# MCU.net
KiCad netlist of a schematic drawn in Altium Designer
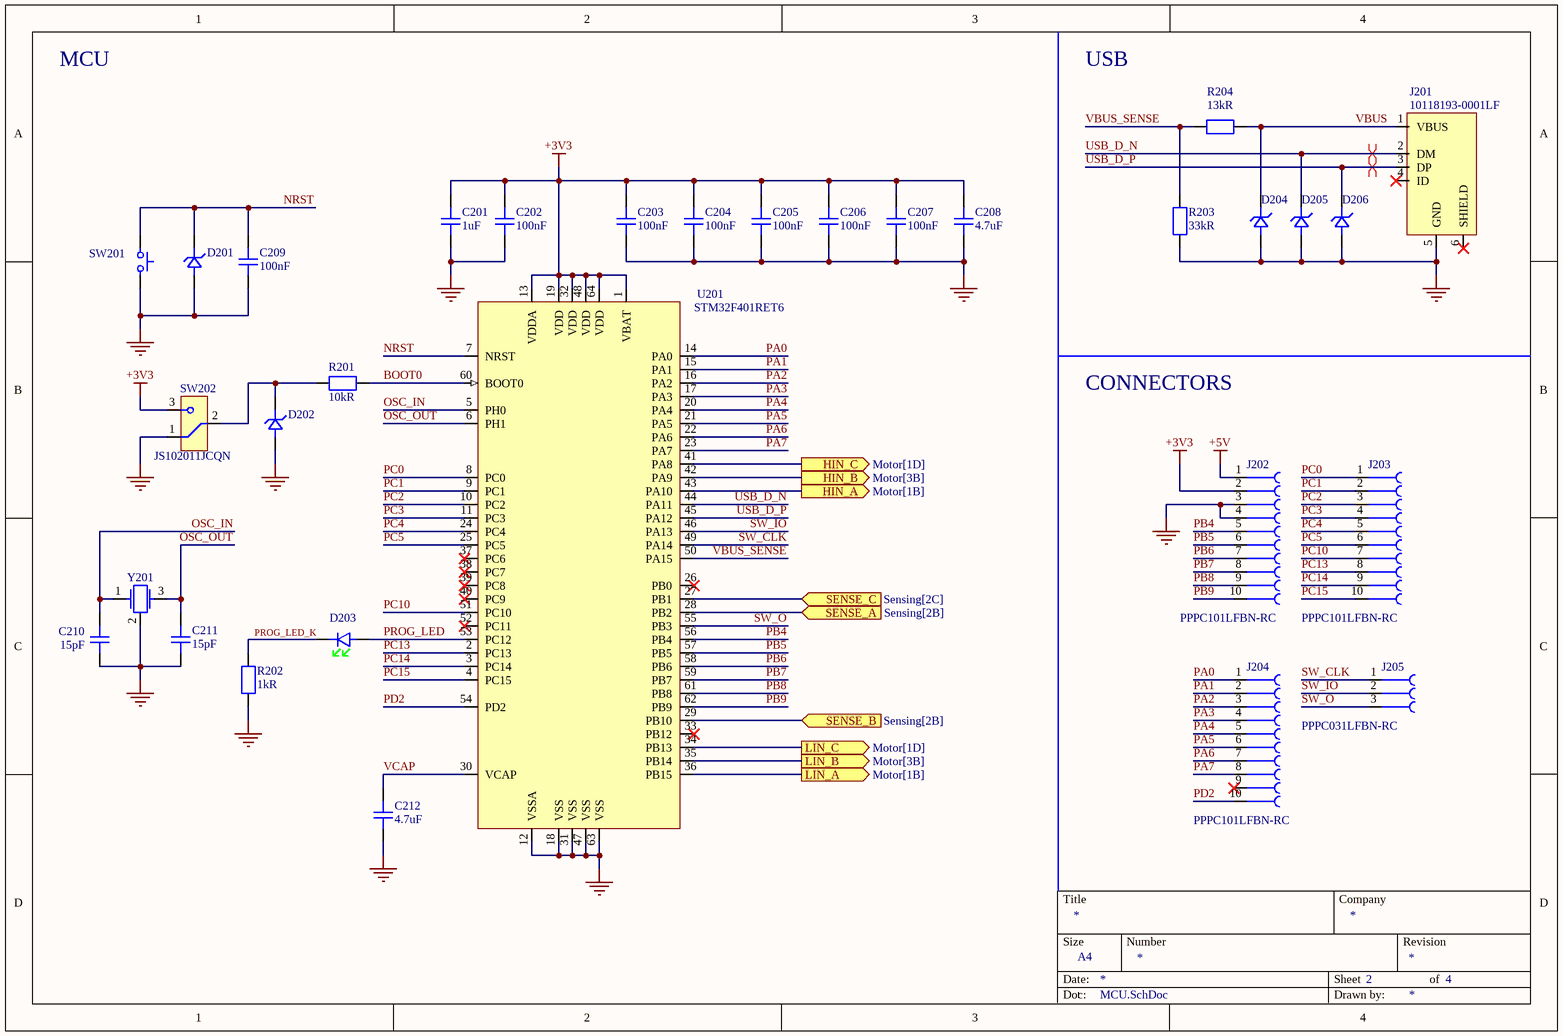
[diagram p0: MCU.SchDoc]

(export (version "E")
  (design (tool "Eeschema 10.0.6"))
  (components
    (comp (ref "C201")
      (value "1uF")
      (footprint "C_Yageo_CC_0603_A")
      (description "Multilayer Ceramic Capacitor, 1 uF, 16 V, ± 10%, X7R, 0603 [1608 Metric]")
      (fields (field (name "TOLERANCE") "10%") (field (name "VOLTAGE") "16V"))
      (libsource (lib "Dennis Micro Computers") (part "C"))
    )
    (comp (ref "C202")
      (value "100nF")
      (footprint "C_Yageo_CC_0402_A")
      (description "Multilayer Ceramic Capacitor, 0.1 uF, 10 V, ± 20%, X7R, 0402 [1005 Metric]")
      (fields (field (name "TOLERANCE") "20%") (field (name "Comment") "CC0402MRX5R6BB104"))
      (libsource (lib "Dennis Micro Computers") (part "C"))
    )
    (comp (ref "C203")
      (value "100nF")
      (footprint "C_Yageo_CC_0402_A")
      (description "Multilayer Ceramic Capacitor, 0.1 uF, 10 V, ± 20%, X7R, 0402 [1005 Metric]")
      (fields (field (name "TOLERANCE") "20%") (field (name "Comment") "CC0402MRX5R6BB104"))
      (libsource (lib "Dennis Micro Computers") (part "C"))
    )
    (comp (ref "C204")
      (value "100nF")
      (footprint "C_Yageo_CC_0402_A")
      (description "Multilayer Ceramic Capacitor, 0.1 uF, 10 V, ± 20%, X7R, 0402 [1005 Metric]")
      (fields (field (name "TOLERANCE") "20%") (field (name "Comment") "CC0402MRX5R6BB104"))
      (libsource (lib "Dennis Micro Computers") (part "C"))
    )
    (comp (ref "C205")
      (value "100nF")
      (footprint "C_Yageo_CC_0402_A")
      (description "Multilayer Ceramic Capacitor, 0.1 uF, 10 V, ± 20%, X7R, 0402 [1005 Metric]")
      (fields (field (name "TOLERANCE") "20%") (field (name "Comment") "CC0402MRX5R6BB104"))
      (libsource (lib "Dennis Micro Computers") (part "C"))
    )
    (comp (ref "C206")
      (value "100nF")
      (footprint "C_Yageo_CC_0402_A")
      (description "Multilayer Ceramic Capacitor, 0.1 uF, 10 V, ± 20%, X7R, 0402 [1005 Metric]")
      (fields (field (name "TOLERANCE") "20%") (field (name "Comment") "CC0402MRX5R6BB104"))
      (libsource (lib "Dennis Micro Computers") (part "C"))
    )
    (comp (ref "C207")
      (value "100nF")
      (footprint "C_Yageo_CC_0402_A")
      (description "Multilayer Ceramic Capacitor, 0.1 uF, 10 V, ± 20%, X7R, 0402 [1005 Metric]")
      (fields (field (name "TOLERANCE") "20%") (field (name "Comment") "CC0402MRX5R6BB104"))
      (libsource (lib "Dennis Micro Computers") (part "C"))
    )
    (comp (ref "C208")
      (value "4.7uF")
      (footprint "C_Yageo_CC_0402_A")
      (description "Multilayer Ceramic Capacitor, 4.7 uF, 50 V, ± 10%, X5R, 0402 [1005 Metric]")
      (fields (field (name "TOLERANCE") "20%") (field (name "Comment") "CC0402MRX5R6BB475"))
      (libsource (lib "Dennis Micro Computers") (part "C"))
    )
    (comp (ref "C209")
      (value "100nF")
      (footprint "C_Yageo_CC_0402_A")
      (description "Multilayer Ceramic Capacitor, 0.1 uF, 10 V, ± 20%, X7R, 0402 [1005 Metric]")
      (fields (field (name "TOLERANCE") "20%") (field (name "Comment") "CC0402MRX5R6BB104"))
      (libsource (lib "Dennis Micro Computers") (part "C"))
    )
    (comp (ref "C210")
      (value "15pF")
      (footprint "C_Yageo_CC_0402_A")
      (description "Multilayer Ceramic Capacitor, 15 pF, 10 V, ± 5%, X7R, 0402 [1005 Metric]")
      (fields (field (name "TOLERANCE") "5%") (field (name "VOLTAGE") "50V"))
      (libsource (lib "Dennis Micro Computers") (part "C"))
    )
    (comp (ref "C211")
      (value "15pF")
      (footprint "C_Yageo_CC_0402_A")
      (description "Multilayer Ceramic Capacitor, 15 pF, 10 V, ± 5%, X7R, 0402 [1005 Metric]")
      (fields (field (name "TOLERANCE") "5%") (field (name "VOLTAGE") "50V"))
      (libsource (lib "Dennis Micro Computers") (part "C"))
    )
    (comp (ref "C212")
      (value "4.7uF")
      (footprint "C_Yageo_CC_0402_A")
      (description "Multilayer Ceramic Capacitor, 4.7 uF, 50 V, ± 10%, X5R, 0402 [1005 Metric]")
      (fields (field (name "TOLERANCE") "20%") (field (name "Comment") "CC0402MRX5R6BB475"))
      (libsource (lib "Dennis Micro Computers") (part "C"))
    )
    (comp (ref "D201")
      (value "D5V0F1U2S9-7")
      (footprint "D_TVS_Uni_Diodes_SOD-923_B")
      (description "Diode TVS Dual Uni-Dir 5.5V 250000W 2-Pin SOD-923 T/R")
      (libsource (lib "Dennis Micro Computers") (part "D_TVS_Uni"))
    )
    (comp (ref "D202")
      (value "D5V0F1U2S9-7")
      (footprint "D_TVS_Uni_Diodes_SOD-923_B")
      (description "Diode TVS Dual Uni-Dir 5.5V 250000W 2-Pin SOD-923 T/R")
      (libsource (lib "Dennis Micro Computers") (part "D_TVS_Uni"))
    )
    (comp (ref "D203")
      (value "150080GS75000")
      (footprint "D_LED_We_150080GS75000")
      (description "WURTH ELEKTRONIK - 150080GS75000 - LED, Green, SMD, 0805, 30 mA, 3.2 V, 520 nm")
      (libsource (lib "Dennis Micro Computers") (part "D_LED_Green"))
    )
    (comp (ref "D204")
      (value "D5V0F1U2S9-7")
      (footprint "D_TVS_Uni_Diodes_SOD-923_B")
      (description "Diode TVS Dual Uni-Dir 5.5V 250000W 2-Pin SOD-923 T/R")
      (libsource (lib "Dennis Micro Computers") (part "D_TVS_Uni"))
    )
    (comp (ref "D205")
      (value "D5V0F1U2S9-7")
      (footprint "D_TVS_Uni_Diodes_SOD-923_B")
      (description "Diode TVS Dual Uni-Dir 5.5V 250000W 2-Pin SOD-923 T/R")
      (libsource (lib "Dennis Micro Computers") (part "D_TVS_Uni"))
    )
    (comp (ref "D206")
      (value "D5V0F1U2S9-7")
      (footprint "D_TVS_Uni_Diodes_SOD-923_B")
      (description "Diode TVS Dual Uni-Dir 5.5V 250000W 2-Pin SOD-923 T/R")
      (libsource (lib "Dennis Micro Computers") (part "D_TVS_Uni"))
    )
    (comp (ref "J201")
      (value "10118193-0001LF")
      (footprint "J_USB_Micro-B_Amphenol_10118193-0001LF")
      (description "Usb Connector, 5 Contact(S), Female, Right Angle, Surface Mount Terminal, Locking, Receptacle")
      (libsource (lib "Dennis Micro Computers") (part "J_USB2_B_Micro"))
    )
    (comp (ref "J202")
      (value "PPPC101LFBN-RC")
      (footprint "J_Sullins_01x07_Socket_2.54mm")
      (description "10 Position Total Single Row 2.54 mm Pitch Straight Female Header")
      (libsource (lib "Dennis Micro Computers") (part "J_01x10_Socket"))
    )
    (comp (ref "J203")
      (value "PPPC101LFBN-RC")
      (footprint "J_Sullins_01x07_Socket_2.54mm")
      (description "10 Position Total Single Row 2.54 mm Pitch Straight Female Header")
      (libsource (lib "Dennis Micro Computers") (part "J_01x10_Socket"))
    )
    (comp (ref "J204")
      (value "PPPC101LFBN-RC")
      (footprint "J_Sullins_01x07_Socket_2.54mm")
      (description "10 Position Total Single Row 2.54 mm Pitch Straight Female Header")
      (libsource (lib "Dennis Micro Computers") (part "J_01x10_Socket"))
    )
    (comp (ref "J205")
      (value "PPPC031LFBN-RC")
      (footprint "J_Sullins_01x03_Socket_2.54mm")
      (description "3 Position Total Single Row 2.54 mm Pitch Straight Female Header")
      (libsource (lib "Dennis Micro Computers") (part "J_01x03_Socket"))
    )
    (comp (ref "R201")
      (value "10kR")
      (footprint "R_Yageo_RCL_0402_A")
      (description "SMD Chip Resistor, 10 kOhm, ± 1%, 62.5 mW, 0402 [1005 Metric], Thick Film, General Purpose")
      (fields (field (name "TOLERANCE") "1%") (field (name "Comment") "RC0402FR-0710KL"))
      (libsource (lib "Dennis Micro Computers") (part "R"))
    )
    (comp (ref "R202")
      (value "1kR")
      (footprint "R_Yageo_RCL_0402_A")
      (description "SMD Chip Resistor, 1 kOhm, ± 1%, 62.5 mW, 0402 [1005 Metric], Thick Film, General Purpose")
      (fields (field (name "TOLERANCE") "1%") (field (name "Comment") "RC0402FR-071KL"))
      (libsource (lib "Dennis Micro Computers") (part "R"))
    )
    (comp (ref "R203")
      (value "33kR")
      (footprint "R_Yageo_RCL_0402_A")
      (description "SMD Chip Resistor, 33 kOhm, ± 1%, 63 mW, 0402 [1005 Metric], Thick Film, General Purpose")
      (fields (field (name "TOLERANCE") "1%") (field (name "Comment") "RC0402FR-0733KL"))
      (libsource (lib "Dennis Micro Computers") (part "R"))
    )
    (comp (ref "R204")
      (value "13kR")
      (footprint "R_Yageo_RCL_0402_A")
      (description "SMD Chip Resistor, 13 kOhm, ± 1%, 63 mW, 0402 [1005 Metric], Thick Film, General Purpose")
      (fields (field (name "TOLERANCE") "1%") (field (name "Comment") "RC0402FR-0713KL"))
      (libsource (lib "Dennis Micro Computers") (part "R"))
    )
    (comp (ref "SW201")
      (value "PTS647SN50SMTR2LFS")
      (footprint "SW_Tactitle_SPST_C&K_PTS647SN50SMTR2LFS")
      (description "Switch Tactile N.O. SPST Round Button Gull Wing 0.05A 12VDC 100000Cycles 0.98N SMD T/R")
      (libsource (lib "Dennis Micro Computers") (part "SW_Tactile_SPST"))
    )
    (comp (ref "SW202")
      (value "JS102011JCQN")
      (footprint "SW_Slide_C&K_JS102011JCQN")
      (description "JS Series Sub-Miniature Slide Switch SPDT On-On Top Slide 0.3A 6VDC J-Lead Surface Mount T/R")
      (libsource (lib "Dennis Micro Computers") (part "SW_Slide_SPDT"))
    )
    (comp (ref "U201")
      (value "STM32F401RET6")
      (footprint "U_ST_STM32F401xD/xE_B")
      (description "MCU 32-bit STM32 ARM Cortex M4 RISC 512KB Flash 1.8V/2.5V/3.3V 64-Pin LQFP Tray")
      (libsource (lib "Dennis Micro Computers") (part "U_STM32F401xD/xE"))
    )
    (comp (ref "Y201")
      (value "ECS-240-12-37B-CKY-TR")
      (footprint "Y_Crystal_GND24_ECS_240-12-37B-CKY-TR")
      (description "Crystal 24MHz ±10ppm (Tol) ±10ppm (Stability) 12pF FUND 50Ohm 4-Pin Mini-CSMD T/R")
      (libsource (lib "Dennis Micro Computers") (part "Y_Crystal_GND24"))
    )
  )
  (nets
    (net (code "1") (name "+3V3") (class "Default")
      (node (ref "C201") (pin "2") (pinfunction "2_2") (pintype "passive"))
      (node (ref "C202") (pin "2") (pinfunction "2_2") (pintype "passive"))
      (node (ref "C203") (pin "2") (pinfunction "2_2") (pintype "passive"))
      (node (ref "C204") (pin "2") (pinfunction "2_2") (pintype "passive"))
      (node (ref "C205") (pin "2") (pinfunction "2_2") (pintype "passive"))
      (node (ref "C206") (pin "2") (pinfunction "2_2") (pintype "passive"))
      (node (ref "C207") (pin "2") (pinfunction "2_2") (pintype "passive"))
      (node (ref "C208") (pin "2") (pinfunction "2_2") (pintype "passive"))
      (node (ref "J202") (pin "2") (pinfunction "2_2") (pintype "passive"))
      (node (ref "SW202") (pin "3") (pinfunction "3_3") (pintype "passive"))
      (node (ref "U201") (pin "1") (pinfunction "VBAT_1") (pintype "power_in"))
      (node (ref "U201") (pin "13") (pinfunction "VDDA_13") (pintype "power_in"))
      (node (ref "U201") (pin "19") (pinfunction "VDD_19") (pintype "power_in"))
      (node (ref "U201") (pin "32") (pinfunction "VDD_32") (pintype "power_in"))
      (node (ref "U201") (pin "48") (pinfunction "VDD_48") (pintype "power_in"))
      (node (ref "U201") (pin "64") (pinfunction "VDD_64") (pintype "power_in"))
    )
    (net (code "2") (name "+5V") (class "Default")
      (node (ref "J202") (pin "1") (pinfunction "1_1") (pintype "passive"))
    )
    (net (code "3") (name "/BOOT0") (class "Default")
      (node (ref "R201") (pin "2") (pinfunction "2_2") (pintype "passive"))
      (node (ref "U201") (pin "60") (pinfunction "BOOT0_60") (pintype "input"))
    )
    (net (code "4") (name "/HIN_A") (class "Default")
      (node (ref "U201") (pin "43") (pinfunction "PA10_43") (pintype "bidirectional"))
    )
    (net (code "5") (name "/HIN_B") (class "Default")
      (node (ref "U201") (pin "42") (pinfunction "PA9_42") (pintype "bidirectional"))
    )
    (net (code "6") (name "/HIN_C") (class "Default")
      (node (ref "U201") (pin "41") (pinfunction "PA8_41") (pintype "bidirectional"))
    )
    (net (code "7") (name "/LIN_A") (class "Default")
      (node (ref "U201") (pin "36") (pinfunction "PB15_36") (pintype "bidirectional"))
    )
    (net (code "8") (name "/LIN_B") (class "Default")
      (node (ref "U201") (pin "35") (pinfunction "PB14_35") (pintype "bidirectional"))
    )
    (net (code "9") (name "/LIN_C") (class "Default")
      (node (ref "U201") (pin "34") (pinfunction "PB13_34") (pintype "bidirectional"))
    )
    (net (code "10") (name "/NRST") (class "Default")
      (node (ref "C209") (pin "2") (pinfunction "2_2") (pintype "passive"))
      (node (ref "D201") (pin "1") (pinfunction "1_1") (pintype "passive"))
      (node (ref "SW201") (pin "1") (pinfunction "1_1") (pintype "passive"))
      (node (ref "U201") (pin "7") (pinfunction "NRST_7") (pintype "bidirectional"))
    )
    (net (code "11") (name "/OSC_IN") (class "Default")
      (node (ref "C210") (pin "2") (pinfunction "2_2") (pintype "passive"))
      (node (ref "U201") (pin "5") (pinfunction "PH0_5") (pintype "bidirectional"))
      (node (ref "Y201") (pin "1") (pinfunction "1_1") (pintype "passive"))
    )
    (net (code "12") (name "/OSC_OUT") (class "Default")
      (node (ref "C211") (pin "2") (pinfunction "2_2") (pintype "passive"))
      (node (ref "U201") (pin "6") (pinfunction "PH1_6") (pintype "bidirectional"))
      (node (ref "Y201") (pin "3") (pinfunction "3_3") (pintype "passive"))
    )
    (net (code "13") (name "/PA0") (class "Default")
      (node (ref "J204") (pin "1") (pinfunction "1_1") (pintype "passive"))
      (node (ref "U201") (pin "14") (pinfunction "PA0_14") (pintype "bidirectional"))
    )
    (net (code "14") (name "/PA1") (class "Default")
      (node (ref "J204") (pin "2") (pinfunction "2_2") (pintype "passive"))
      (node (ref "U201") (pin "15") (pinfunction "PA1_15") (pintype "bidirectional"))
    )
    (net (code "15") (name "/PA2") (class "Default")
      (node (ref "J204") (pin "3") (pinfunction "3_3") (pintype "passive"))
      (node (ref "U201") (pin "16") (pinfunction "PA2_16") (pintype "bidirectional"))
    )
    (net (code "16") (name "/PA3") (class "Default")
      (node (ref "J204") (pin "4") (pinfunction "4_4") (pintype "passive"))
      (node (ref "U201") (pin "17") (pinfunction "PA3_17") (pintype "bidirectional"))
    )
    (net (code "17") (name "/PA4") (class "Default")
      (node (ref "J204") (pin "5") (pinfunction "5_5") (pintype "passive"))
      (node (ref "U201") (pin "20") (pinfunction "PA4_20") (pintype "bidirectional"))
    )
    (net (code "18") (name "/PA5") (class "Default")
      (node (ref "J204") (pin "6") (pinfunction "6_6") (pintype "passive"))
      (node (ref "U201") (pin "21") (pinfunction "PA5_21") (pintype "bidirectional"))
    )
    (net (code "19") (name "/PA6") (class "Default")
      (node (ref "J204") (pin "7") (pinfunction "7_7") (pintype "passive"))
      (node (ref "U201") (pin "22") (pinfunction "PA6_22") (pintype "bidirectional"))
    )
    (net (code "20") (name "/PA7") (class "Default")
      (node (ref "J204") (pin "8") (pinfunction "8_8") (pintype "passive"))
      (node (ref "U201") (pin "23") (pinfunction "PA7_23") (pintype "bidirectional"))
    )
    (net (code "21") (name "/PB4") (class "Default")
      (node (ref "J202") (pin "5") (pinfunction "5_5") (pintype "passive"))
      (node (ref "U201") (pin "56") (pinfunction "PB4_56") (pintype "bidirectional"))
    )
    (net (code "22") (name "/PB5") (class "Default")
      (node (ref "J202") (pin "6") (pinfunction "6_6") (pintype "passive"))
      (node (ref "U201") (pin "57") (pinfunction "PB5_57") (pintype "bidirectional"))
    )
    (net (code "23") (name "/PB6") (class "Default")
      (node (ref "J202") (pin "7") (pinfunction "7_7") (pintype "passive"))
      (node (ref "U201") (pin "58") (pinfunction "PB6_58") (pintype "bidirectional"))
    )
    (net (code "24") (name "/PB7") (class "Default")
      (node (ref "J202") (pin "8") (pinfunction "8_8") (pintype "passive"))
      (node (ref "U201") (pin "59") (pinfunction "PB7_59") (pintype "bidirectional"))
    )
    (net (code "25") (name "/PB8") (class "Default")
      (node (ref "J202") (pin "9") (pinfunction "9_9") (pintype "passive"))
      (node (ref "U201") (pin "61") (pinfunction "PB8_61") (pintype "bidirectional"))
    )
    (net (code "26") (name "/PB9") (class "Default")
      (node (ref "J202") (pin "10") (pinfunction "10_10") (pintype "passive"))
      (node (ref "U201") (pin "62") (pinfunction "PB9_62") (pintype "bidirectional"))
    )
    (net (code "27") (name "/PC0") (class "Default")
      (node (ref "J203") (pin "1") (pinfunction "1_1") (pintype "passive"))
      (node (ref "U201") (pin "8") (pinfunction "PC0_8") (pintype "bidirectional"))
    )
    (net (code "28") (name "/PC1") (class "Default")
      (node (ref "J203") (pin "2") (pinfunction "2_2") (pintype "passive"))
      (node (ref "U201") (pin "9") (pinfunction "PC1_9") (pintype "bidirectional"))
    )
    (net (code "29") (name "/PC2") (class "Default")
      (node (ref "J203") (pin "3") (pinfunction "3_3") (pintype "passive"))
      (node (ref "U201") (pin "10") (pinfunction "PC2_10") (pintype "bidirectional"))
    )
    (net (code "30") (name "/PC3") (class "Default")
      (node (ref "J203") (pin "4") (pinfunction "4_4") (pintype "passive"))
      (node (ref "U201") (pin "11") (pinfunction "PC3_11") (pintype "bidirectional"))
    )
    (net (code "31") (name "/PC4") (class "Default")
      (node (ref "J203") (pin "5") (pinfunction "5_5") (pintype "passive"))
      (node (ref "U201") (pin "24") (pinfunction "PC4_24") (pintype "bidirectional"))
    )
    (net (code "32") (name "/PC5") (class "Default")
      (node (ref "J203") (pin "6") (pinfunction "6_6") (pintype "passive"))
      (node (ref "U201") (pin "25") (pinfunction "PC5_25") (pintype "bidirectional"))
    )
    (net (code "33") (name "/PC10") (class "Default")
      (node (ref "J203") (pin "7") (pinfunction "7_7") (pintype "passive"))
      (node (ref "U201") (pin "51") (pinfunction "PC10_51") (pintype "bidirectional"))
    )
    (net (code "34") (name "/PC13") (class "Default")
      (node (ref "J203") (pin "8") (pinfunction "8_8") (pintype "passive"))
      (node (ref "U201") (pin "2") (pinfunction "PC13_2") (pintype "bidirectional"))
    )
    (net (code "35") (name "/PC14") (class "Default")
      (node (ref "J203") (pin "9") (pinfunction "9_9") (pintype "passive"))
      (node (ref "U201") (pin "3") (pinfunction "PC14_3") (pintype "bidirectional"))
    )
    (net (code "36") (name "/PC15") (class "Default")
      (node (ref "J203") (pin "10") (pinfunction "10_10") (pintype "passive"))
      (node (ref "U201") (pin "4") (pinfunction "PC15_4") (pintype "bidirectional"))
    )
    (net (code "37") (name "/PD2") (class "Default")
      (node (ref "J204") (pin "10") (pinfunction "10_10") (pintype "passive"))
      (node (ref "U201") (pin "54") (pinfunction "PD2_54") (pintype "bidirectional"))
    )
    (net (code "38") (name "/PROG_LED") (class "Default")
      (node (ref "D203") (pin "1") (pinfunction "1_1") (pintype "passive"))
      (node (ref "U201") (pin "53") (pinfunction "PC12_53") (pintype "bidirectional"))
    )
    (net (code "39") (name "/PROG_LED_K") (class "Default")
      (node (ref "D203") (pin "2") (pinfunction "2_2") (pintype "passive"))
      (node (ref "R202") (pin "2") (pinfunction "2_2") (pintype "passive"))
    )
    (net (code "40") (name "/SENSE_A") (class "Default")
      (node (ref "U201") (pin "28") (pinfunction "PB2_28") (pintype "bidirectional"))
    )
    (net (code "41") (name "/SENSE_B") (class "Default")
      (node (ref "U201") (pin "29") (pinfunction "PB10_29") (pintype "bidirectional"))
    )
    (net (code "42") (name "/SENSE_C") (class "Default")
      (node (ref "U201") (pin "27") (pinfunction "PB1_27") (pintype "bidirectional"))
    )
    (net (code "43") (name "/SW_CLK") (class "Default")
      (node (ref "J205") (pin "1") (pinfunction "1_1") (pintype "passive"))
      (node (ref "U201") (pin "49") (pinfunction "PA14_49") (pintype "bidirectional"))
    )
    (net (code "44") (name "/SW_IO") (class "Default")
      (node (ref "J205") (pin "2") (pinfunction "2_2") (pintype "passive"))
      (node (ref "U201") (pin "46") (pinfunction "PA13_46") (pintype "bidirectional"))
    )
    (net (code "45") (name "/SW_O") (class "Default")
      (node (ref "J205") (pin "3") (pinfunction "3_3") (pintype "passive"))
      (node (ref "U201") (pin "55") (pinfunction "PB3_55") (pintype "bidirectional"))
    )
    (net (code "46") (name "/USB_D_N") (class "Default")
      (node (ref "D205") (pin "1") (pinfunction "1_1") (pintype "passive"))
      (node (ref "J201") (pin "2") (pinfunction "DM_2") (pintype "bidirectional"))
      (node (ref "U201") (pin "44") (pinfunction "PA11_44") (pintype "bidirectional"))
    )
    (net (code "47") (name "/USB_D_P") (class "Default")
      (node (ref "D206") (pin "1") (pinfunction "1_1") (pintype "passive"))
      (node (ref "J201") (pin "3") (pinfunction "DP_3") (pintype "bidirectional"))
      (node (ref "U201") (pin "45") (pinfunction "PA12_45") (pintype "bidirectional"))
    )
    (net (code "48") (name "/VBUS") (class "Default")
      (node (ref "D204") (pin "1") (pinfunction "1_1") (pintype "passive"))
      (node (ref "J201") (pin "1") (pinfunction "VBUS_1") (pintype "power_in"))
      (node (ref "R204") (pin "2") (pinfunction "2_2") (pintype "passive"))
    )
    (net (code "49") (name "/VBUS_SENSE") (class "Default")
      (node (ref "R203") (pin "2") (pinfunction "2_2") (pintype "passive"))
      (node (ref "R204") (pin "1") (pinfunction "1_1") (pintype "passive"))
      (node (ref "U201") (pin "50") (pinfunction "PA15_50") (pintype "bidirectional"))
    )
    (net (code "50") (name "/VCAP") (class "Default")
      (node (ref "C212") (pin "2") (pinfunction "2_2") (pintype "passive"))
      (node (ref "U201") (pin "30") (pinfunction "VCAP_30") (pintype "power_in"))
    )
    (net (code "51") (name "GND") (class "Default")
      (node (ref "C201") (pin "1") (pinfunction "1_1") (pintype "passive"))
      (node (ref "C202") (pin "1") (pinfunction "1_1") (pintype "passive"))
      (node (ref "C203") (pin "1") (pinfunction "1_1") (pintype "passive"))
      (node (ref "C204") (pin "1") (pinfunction "1_1") (pintype "passive"))
      (node (ref "C205") (pin "1") (pinfunction "1_1") (pintype "passive"))
      (node (ref "C206") (pin "1") (pinfunction "1_1") (pintype "passive"))
      (node (ref "C207") (pin "1") (pinfunction "1_1") (pintype "passive"))
      (node (ref "C208") (pin "1") (pinfunction "1_1") (pintype "passive"))
      (node (ref "C209") (pin "1") (pinfunction "1_1") (pintype "passive"))
      (node (ref "C210") (pin "1") (pinfunction "1_1") (pintype "passive"))
      (node (ref "C211") (pin "1") (pinfunction "1_1") (pintype "passive"))
      (node (ref "C212") (pin "1") (pinfunction "1_1") (pintype "passive"))
      (node (ref "D201") (pin "2") (pinfunction "2_2") (pintype "passive"))
      (node (ref "D202") (pin "2") (pinfunction "2_2") (pintype "passive"))
      (node (ref "D204") (pin "2") (pinfunction "2_2") (pintype "passive"))
      (node (ref "D205") (pin "2") (pinfunction "2_2") (pintype "passive"))
      (node (ref "D206") (pin "2") (pinfunction "2_2") (pintype "passive"))
      (node (ref "J201") (pin "5") (pinfunction "GND_5") (pintype "power_in"))
      (node (ref "J202") (pin "3") (pinfunction "3_3") (pintype "passive"))
      (node (ref "J202") (pin "4") (pinfunction "4_4") (pintype "passive"))
      (node (ref "R202") (pin "1") (pinfunction "1_1") (pintype "passive"))
      (node (ref "R203") (pin "1") (pinfunction "1_1") (pintype "passive"))
      (node (ref "SW201") (pin "2") (pinfunction "2_2") (pintype "passive"))
      (node (ref "SW202") (pin "1") (pinfunction "1_1") (pintype "passive"))
      (node (ref "U201") (pin "12") (pinfunction "VSSA_12") (pintype "power_in"))
      (node (ref "U201") (pin "18") (pinfunction "VSS_18") (pintype "power_in"))
      (node (ref "U201") (pin "31") (pinfunction "VSS_31") (pintype "power_in"))
      (node (ref "U201") (pin "47") (pinfunction "VSS_47") (pintype "power_in"))
      (node (ref "U201") (pin "63") (pinfunction "VSS_63") (pintype "power_in"))
      (node (ref "Y201") (pin "2") (pinfunction "2_2") (pintype "passive"))
    )
    (net (code "52") (name "Net-(D202-Pad1)") (class "Default")
      (node (ref "D202") (pin "1") (pinfunction "1_1") (pintype "passive"))
      (node (ref "R201") (pin "1") (pinfunction "1_1") (pintype "passive"))
      (node (ref "SW202") (pin "2") (pinfunction "2_2") (pintype "passive"))
    )
    (net (code "53") (name "unconnected-(J201-ID-Pad4)") (class "Default")
      (node (ref "J201") (pin "4") (pinfunction "ID_4") (pintype "passive+no_connect"))
    )
    (net (code "54") (name "unconnected-(J201-SHIELD-Pad6)") (class "Default")
      (node (ref "J201") (pin "6") (pinfunction "SHIELD_6") (pintype "passive+no_connect"))
    )
    (net (code "55") (name "unconnected-(J204-Pad9)") (class "Default")
      (node (ref "J204") (pin "9") (pinfunction "9_9") (pintype "passive+no_connect"))
    )
    (net (code "56") (name "unconnected-(U201-PB0-Pad26)") (class "Default")
      (node (ref "U201") (pin "26") (pinfunction "PB0_26") (pintype "bidirectional+no_connect"))
    )
    (net (code "57") (name "unconnected-(U201-PB12-Pad33)") (class "Default")
      (node (ref "U201") (pin "33") (pinfunction "PB12_33") (pintype "bidirectional+no_connect"))
    )
    (net (code "58") (name "unconnected-(U201-PC6-Pad37)") (class "Default")
      (node (ref "U201") (pin "37") (pinfunction "PC6_37") (pintype "bidirectional+no_connect"))
    )
    (net (code "59") (name "unconnected-(U201-PC7-Pad38)") (class "Default")
      (node (ref "U201") (pin "38") (pinfunction "PC7_38") (pintype "bidirectional+no_connect"))
    )
    (net (code "60") (name "unconnected-(U201-PC8-Pad39)") (class "Default")
      (node (ref "U201") (pin "39") (pinfunction "PC8_39") (pintype "bidirectional+no_connect"))
    )
    (net (code "61") (name "unconnected-(U201-PC9-Pad40)") (class "Default")
      (node (ref "U201") (pin "40") (pinfunction "PC9_40") (pintype "bidirectional+no_connect"))
    )
    (net (code "62") (name "unconnected-(U201-PC11-Pad52)") (class "Default")
      (node (ref "U201") (pin "52") (pinfunction "PC11_52") (pintype "bidirectional+no_connect"))
    )
  )
)
